# main.net
KiCad netlist of a schematic drawn in Altium Designer
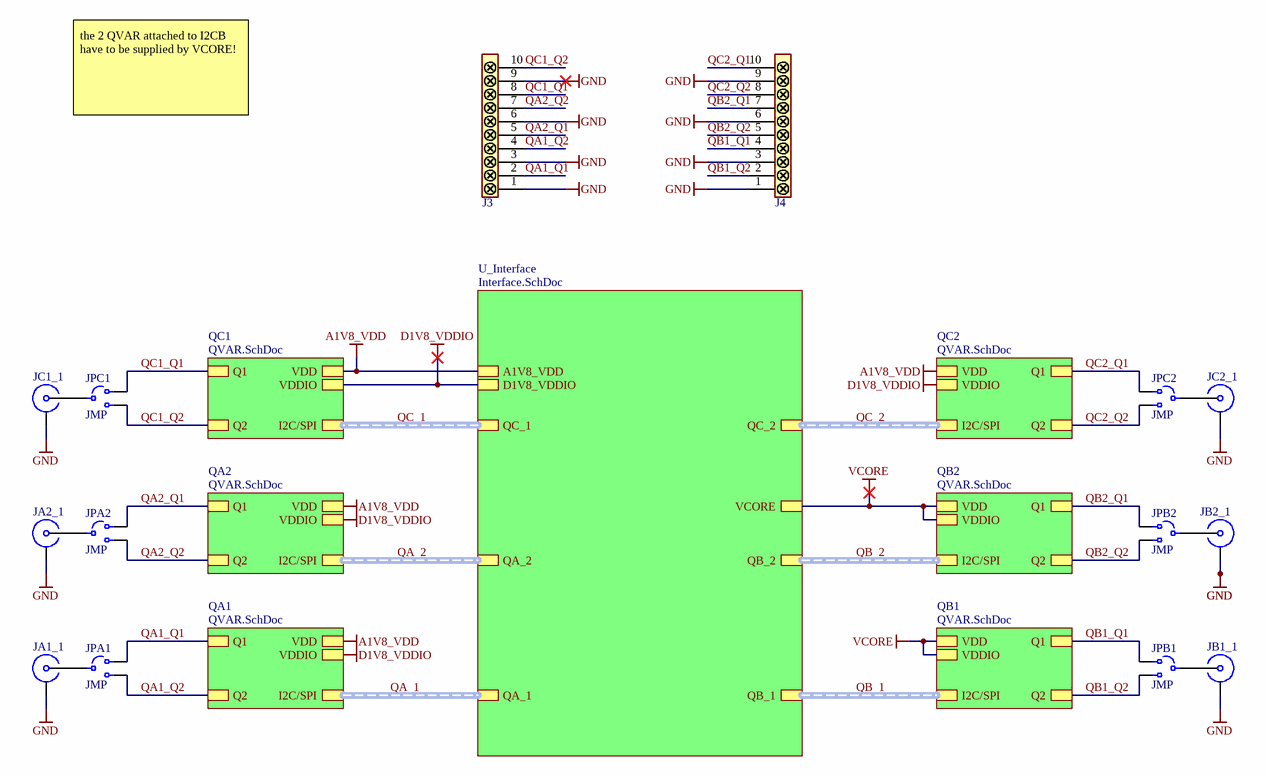
[diagram p0: main.SchDoc]

(export (version "E")
  (design (tool "Eeschema 10.0.6"))
  (components
    (comp (ref "J3")
      (value "FTS-110-01-L-S")
      (footprint "SAMTEC-FTS-110-01-L-S")
      (description "Pinheader 10 pin, 1.27mm")
      (fields (field (name "MANUFACTURER") "Samtec"))
      (libsource (lib "6QChan_vitalcore_backpack") (part "FTS-110-01-L-S"))
    )
    (comp (ref "J4")
      (value "FTS-110-01-L-S")
      (footprint "SAMTEC-FTS-110-01-L-S")
      (description "Pinheader 10 pin, 1.27mm")
      (fields (field (name "MANUFACTURER") "Samtec"))
      (libsource (lib "") (part "FTS-110-01-L-S_1"))
    )
    (comp (ref "JA1_1")
      (value "CONMHF1-SMD-G-T")
      (footprint "C-CONMHF1-SMD-G-T")
      (description "Conn Umc Jack Str SMD")
      (fields (field (name "MANUFACTURER") "TE Connectivity"))
      (libsource (lib "6QChan_vitalcore_backpack") (part "CONMHF1-SMD-G-T"))
    )
    (comp (ref "JA2_1")
      (value "CONMHF1-SMD-G-T")
      (footprint "C-CONMHF1-SMD-G-T")
      (description "Conn Umc Jack Str SMD")
      (fields (field (name "MANUFACTURER") "TE Connectivity"))
      (libsource (lib "6QChan_vitalcore_backpack") (part "CONMHF1-SMD-G-T"))
    )
    (comp (ref "JB1_1")
      (value "CONMHF1-SMD-G-T")
      (footprint "C-CONMHF1-SMD-G-T")
      (description "Conn Umc Jack Str SMD")
      (fields (field (name "MANUFACTURER") "TE Connectivity"))
      (libsource (lib "") (part "CONMHF1-SMD-G-T_1"))
    )
    (comp (ref "JB2_1")
      (value "CONMHF1-SMD-G-T")
      (footprint "C-CONMHF1-SMD-G-T")
      (description "Conn Umc Jack Str SMD")
      (fields (field (name "MANUFACTURER") "TE Connectivity"))
      (libsource (lib "") (part "CONMHF1-SMD-G-T_1"))
    )
    (comp (ref "JC1_1")
      (value "CONMHF1-SMD-G-T")
      (footprint "C-CONMHF1-SMD-G-T")
      (description "Conn Umc Jack Str SMD")
      (fields (field (name "MANUFACTURER") "TE Connectivity"))
      (libsource (lib "6QChan_vitalcore_backpack") (part "CONMHF1-SMD-G-T"))
    )
    (comp (ref "JC2_1")
      (value "CONMHF1-SMD-G-T")
      (footprint "C-CONMHF1-SMD-G-T")
      (description "Conn Umc Jack Str SMD")
      (fields (field (name "MANUFACTURER") "TE Connectivity"))
      (libsource (lib "") (part "CONMHF1-SMD-G-T_1"))
    )
    (comp (ref "JPA1")
      (value "JMP")
      (footprint "JMP_0201_3way")
      (description "JMP 0201 3W")
      (fields
        (field (name "MANUFACTURER") "Panasonic")
        (field (name "MANUFACTURER PART NUMBER") "ERJ-1GN0R00C")
      )
      (libsource (lib "6QChan_vitalcore_backpack") (part "JMP_0201_3w"))
    )
    (comp (ref "JPA2")
      (value "JMP")
      (footprint "JMP_0201_3way")
      (description "JMP 0201 3W")
      (fields
        (field (name "MANUFACTURER") "Panasonic")
        (field (name "MANUFACTURER PART NUMBER") "ERJ-1GN0R00C")
      )
      (libsource (lib "6QChan_vitalcore_backpack") (part "JMP_0201_3w"))
    )
    (comp (ref "JPB1")
      (value "JMP")
      (footprint "JMP_0201_3way")
      (description "JMP 0201 3W")
      (fields
        (field (name "MANUFACTURER") "Panasonic")
        (field (name "MANUFACTURER PART NUMBER") "ERJ-1GN0R00C")
      )
      (libsource (lib "") (part "JMP_0201_3w_1"))
    )
    (comp (ref "JPB2")
      (value "JMP")
      (footprint "JMP_0201_3way")
      (description "JMP 0201 3W")
      (fields
        (field (name "MANUFACTURER") "Panasonic")
        (field (name "MANUFACTURER PART NUMBER") "ERJ-1GN0R00C")
      )
      (libsource (lib "") (part "JMP_0201_3w_1"))
    )
    (comp (ref "JPC1")
      (value "JMP")
      (footprint "JMP_0201_3way")
      (description "JMP 0201 3W")
      (fields
        (field (name "MANUFACTURER") "Panasonic")
        (field (name "MANUFACTURER PART NUMBER") "ERJ-1GN0R00C")
      )
      (libsource (lib "6QChan_vitalcore_backpack") (part "JMP_0201_3w"))
    )
    (comp (ref "JPC2")
      (value "JMP")
      (footprint "JMP_0201_3way")
      (description "JMP 0201 3W")
      (fields
        (field (name "MANUFACTURER") "Panasonic")
        (field (name "MANUFACTURER PART NUMBER") "ERJ-1GN0R00C")
      )
      (libsource (lib "") (part "JMP_0201_3w_1"))
    )
  )
  (nets
    (net (code "7") (name "/QA1_Q1") (class "Default")
      (node (ref "J3") (pin "2") (pintype "passive"))
      (node (ref "JPA1") (pin "1") (pinfunction "1_1") (pintype "passive"))
    )
    (net (code "8") (name "/QA1_Q2") (class "Default")
      (node (ref "J3") (pin "4") (pintype "passive"))
      (node (ref "JPA1") (pin "3") (pinfunction "3_3") (pintype "passive"))
    )
    (net (code "9") (name "/QA2_Q1") (class "Default")
      (node (ref "J3") (pin "5") (pintype "passive"))
      (node (ref "JPA2") (pin "1") (pinfunction "1_1") (pintype "passive"))
    )
    (net (code "10") (name "/QA2_Q2") (class "Default")
      (node (ref "J3") (pin "7") (pintype "passive"))
      (node (ref "JPA2") (pin "3") (pinfunction "3_3") (pintype "passive"))
    )
    (net (code "11") (name "/QB1_Q1") (class "Default")
      (node (ref "J4") (pin "4") (pintype "passive"))
      (node (ref "JPB1") (pin "1") (pinfunction "1_1") (pintype "passive"))
    )
    (net (code "12") (name "/QB1_Q2") (class "Default")
      (node (ref "J4") (pin "2") (pintype "passive"))
      (node (ref "JPB1") (pin "3") (pinfunction "3_3") (pintype "passive"))
    )
    (net (code "13") (name "/QB2_Q1") (class "Default")
      (node (ref "J4") (pin "7") (pintype "passive"))
      (node (ref "JPB2") (pin "1") (pinfunction "1_1") (pintype "passive"))
    )
    (net (code "14") (name "/QB2_Q2") (class "Default")
      (node (ref "J4") (pin "5") (pintype "passive"))
      (node (ref "JPB2") (pin "3") (pinfunction "3_3") (pintype "passive"))
    )
    (net (code "15") (name "/QC1_Q1") (class "Default")
      (node (ref "J3") (pin "8") (pintype "passive"))
      (node (ref "JPC1") (pin "1") (pinfunction "1_1") (pintype "passive"))
    )
    (net (code "16") (name "/QC1_Q2") (class "Default")
      (node (ref "J3") (pin "10") (pintype "passive"))
      (node (ref "JPC1") (pin "3") (pinfunction "3_3") (pintype "passive"))
    )
    (net (code "17") (name "/QC2_Q1") (class "Default")
      (node (ref "J4") (pin "10") (pintype "passive"))
      (node (ref "JPC2") (pin "1") (pinfunction "1_1") (pintype "passive"))
    )
    (net (code "18") (name "/QC2_Q2") (class "Default")
      (node (ref "J4") (pin "8") (pintype "passive"))
      (node (ref "JPC2") (pin "3") (pinfunction "3_3") (pintype "passive"))
    )
    (net (code "27") (name "GND") (class "Default")
      (node (ref "J3") (pin "1") (pintype "passive"))
      (node (ref "J3") (pin "3") (pintype "passive"))
      (node (ref "J3") (pin "6") (pintype "passive"))
      (node (ref "J3") (pin "9") (pintype "passive"))
      (node (ref "J4") (pin "1") (pintype "passive"))
      (node (ref "J4") (pin "3") (pintype "passive"))
      (node (ref "J4") (pin "6") (pintype "passive"))
      (node (ref "J4") (pin "9") (pintype "passive"))
      (node (ref "JA1_1") (pin "G") (pinfunction "G_G") (pintype "passive"))
      (node (ref "JA2_1") (pin "G") (pinfunction "G_G") (pintype "passive"))
      (node (ref "JB1_1") (pin "G") (pinfunction "G_G") (pintype "passive"))
      (node (ref "JB2_1") (pin "G") (pinfunction "G_G") (pintype "passive"))
      (node (ref "JC1_1") (pin "G") (pinfunction "G_G") (pintype "passive"))
      (node (ref "JC2_1") (pin "G") (pinfunction "G_G") (pintype "passive"))
    )
    (net (code "28") (name "Net-(JA1_1-PadS)") (class "Default")
      (node (ref "JA1_1") (pin "S") (pinfunction "S_S") (pintype "passive"))
      (node (ref "JPA1") (pin "2") (pinfunction "2_2") (pintype "passive"))
    )
    (net (code "29") (name "Net-(JA2_1-PadS)") (class "Default")
      (node (ref "JA2_1") (pin "S") (pinfunction "S_S") (pintype "passive"))
      (node (ref "JPA2") (pin "2") (pinfunction "2_2") (pintype "passive"))
    )
    (net (code "30") (name "Net-(JB1_1-PadS)") (class "Default")
      (node (ref "JB1_1") (pin "S") (pinfunction "S_S") (pintype "passive"))
      (node (ref "JPB1") (pin "2") (pinfunction "2_2") (pintype "passive"))
    )
    (net (code "31") (name "Net-(JB2_1-PadS)") (class "Default")
      (node (ref "JB2_1") (pin "S") (pinfunction "S_S") (pintype "passive"))
      (node (ref "JPB2") (pin "2") (pinfunction "2_2") (pintype "passive"))
    )
    (net (code "32") (name "Net-(JC1_1-PadS)") (class "Default")
      (node (ref "JC1_1") (pin "S") (pinfunction "S_S") (pintype "passive"))
      (node (ref "JPC1") (pin "2") (pinfunction "2_2") (pintype "passive"))
    )
    (net (code "33") (name "Net-(JC2_1-PadS)") (class "Default")
      (node (ref "JC2_1") (pin "S") (pinfunction "S_S") (pintype "passive"))
      (node (ref "JPC2") (pin "2") (pinfunction "2_2") (pintype "passive"))
    )
  )
)
